# Schematic.net
KiCad netlist of a schematic drawn in Altium Designer
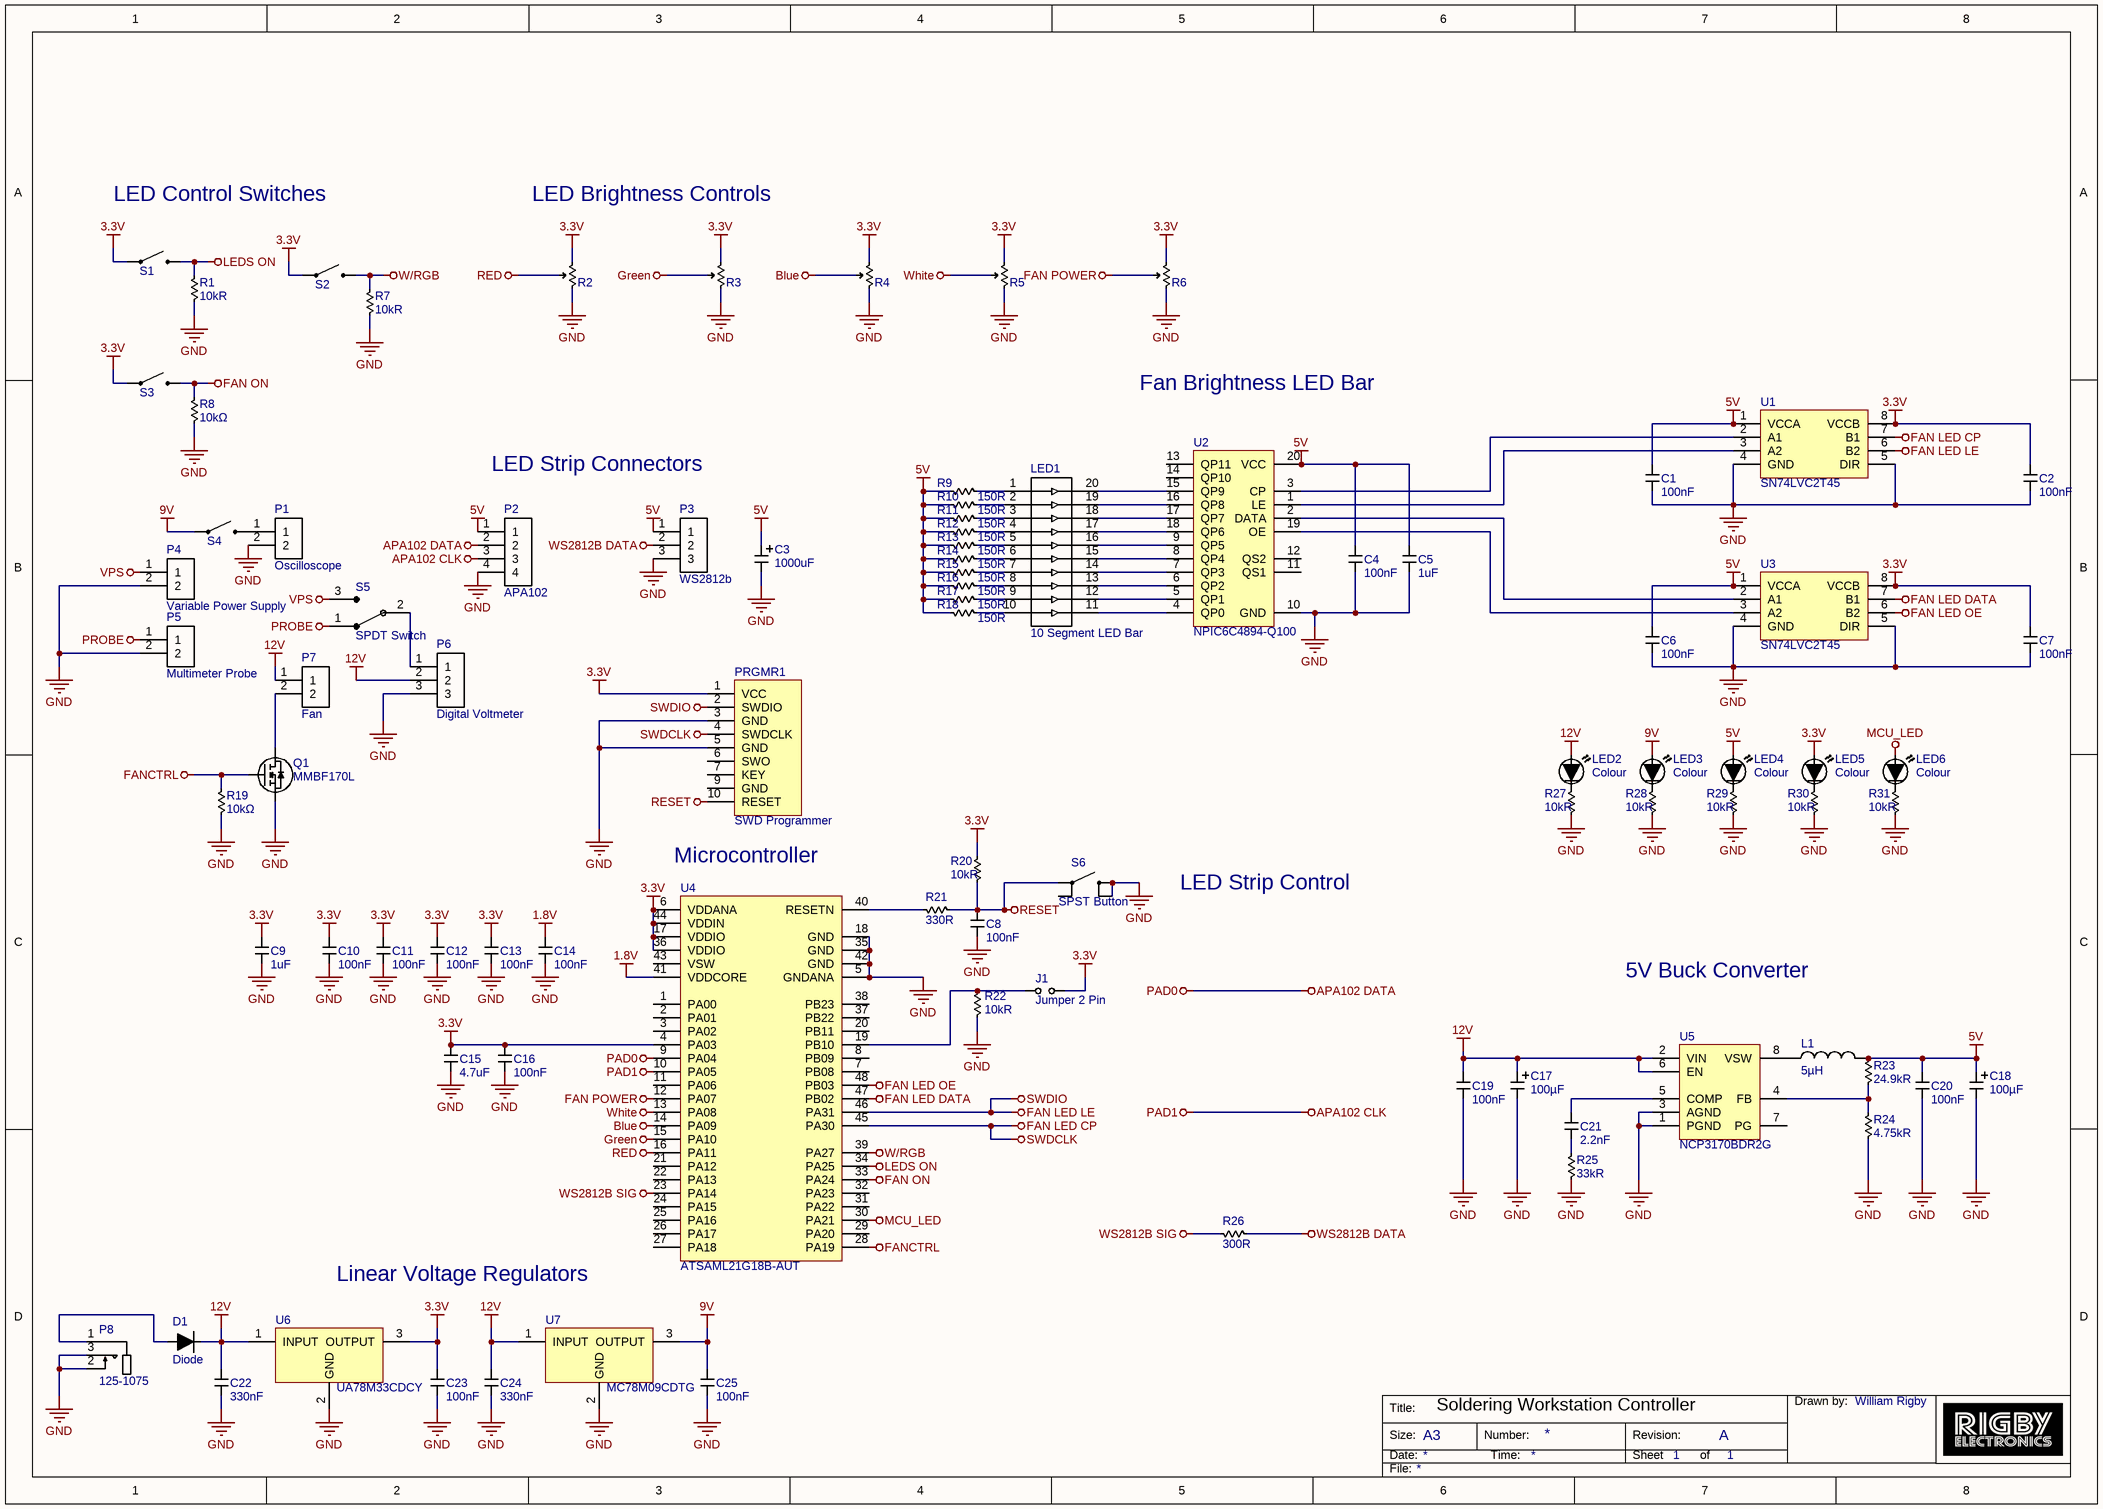
[diagram p0: Schematic.SchDoc]

(export (version "E")
  (design (tool "Eeschema 10.0.6"))
  (components
    (comp (ref "C1")
      (value "100nF")
      (footprint "0603")
      (description "Capacitor")
      (libsource (lib "Rigby Electronics Schematic Library") (part "Capacitor"))
    )
    (comp (ref "C2")
      (value "100nF")
      (footprint "0603")
      (description "Capacitor")
      (libsource (lib "Rigby Electronics Schematic Library") (part "Capacitor"))
    )
    (comp (ref "C3")
      (value "1000uF")
      (footprint "RS 711-0987")
      (description "Polarized Capacitor")
      (libsource (lib "Rigby Electronics Schematic Library") (part "Capacitor Polarized"))
    )
    (comp (ref "C4")
      (value "100nF")
      (footprint "0603")
      (description "Capacitor")
      (libsource (lib "Rigby Electronics Schematic Library") (part "Capacitor"))
    )
    (comp (ref "C5")
      (value "1uF")
      (footprint "0805")
      (description "Capacitor")
      (libsource (lib "Rigby Electronics Schematic Library") (part "Capacitor"))
    )
    (comp (ref "C6")
      (value "100nF")
      (footprint "0603")
      (description "Capacitor")
      (libsource (lib "Rigby Electronics Schematic Library") (part "Capacitor"))
    )
    (comp (ref "C7")
      (value "100nF")
      (footprint "0603")
      (description "Capacitor")
      (libsource (lib "Rigby Electronics Schematic Library") (part "Capacitor"))
    )
    (comp (ref "C8")
      (value "100nF")
      (footprint "0603")
      (description "Capacitor")
      (libsource (lib "Rigby Electronics Schematic Library") (part "Capacitor"))
    )
    (comp (ref "C9")
      (value "1uF")
      (footprint "0805")
      (description "Capacitor")
      (libsource (lib "Rigby Electronics Schematic Library") (part "Capacitor"))
    )
    (comp (ref "C10")
      (value "100nF")
      (footprint "0603")
      (description "Capacitor")
      (libsource (lib "Rigby Electronics Schematic Library") (part "Capacitor"))
    )
    (comp (ref "C11")
      (value "100nF")
      (footprint "0603")
      (description "Capacitor")
      (libsource (lib "Rigby Electronics Schematic Library") (part "Capacitor"))
    )
    (comp (ref "C12")
      (value "100nF")
      (footprint "0603")
      (description "Capacitor")
      (libsource (lib "Rigby Electronics Schematic Library") (part "Capacitor"))
    )
    (comp (ref "C13")
      (value "100nF")
      (footprint "0603")
      (description "Capacitor")
      (libsource (lib "Rigby Electronics Schematic Library") (part "Capacitor"))
    )
    (comp (ref "C14")
      (value "100nF")
      (footprint "0603")
      (description "Capacitor")
      (libsource (lib "Rigby Electronics Schematic Library") (part "Capacitor"))
    )
    (comp (ref "C15")
      (value "4.7uF")
      (footprint "0805")
      (description "Capacitor")
      (libsource (lib "Rigby Electronics Schematic Library") (part "Capacitor"))
    )
    (comp (ref "C16")
      (value "100nF")
      (footprint "0603")
      (description "Capacitor")
      (libsource (lib "Rigby Electronics Schematic Library") (part "Capacitor"))
    )
    (comp (ref "C17")
      (value "100µF")
      (footprint "Nichon UCD0J102MNL1GS")
      (description "Polarized Capacitor")
      (libsource (lib "Rigby Electronics Schematic Library") (part "Capacitor Polarized"))
    )
    (comp (ref "C18")
      (value "100µF")
      (footprint "Nichon UCD0J102MNL1GS")
      (description "Polarized Capacitor")
      (libsource (lib "Rigby Electronics Schematic Library") (part "Capacitor Polarized"))
    )
    (comp (ref "C19")
      (value "100nF")
      (footprint "0603")
      (description "Capacitor")
      (libsource (lib "Rigby Electronics Schematic Library") (part "Capacitor"))
    )
    (comp (ref "C20")
      (value "100nF")
      (footprint "0603")
      (description "Capacitor")
      (libsource (lib "Rigby Electronics Schematic Library") (part "Capacitor"))
    )
    (comp (ref "C21")
      (value "2.2nF")
      (footprint "Rigby Electronics Footprint Library:0603")
      (description "Capacitor")
      (libsource (lib "Rigby Electronics Schematic Library") (part "Capacitor"))
    )
    (comp (ref "C22")
      (value "330nF")
      (footprint "Rigby Electronics Footprint Library:0603")
      (description "Capacitor")
      (libsource (lib "Rigby Electronics Schematic Library") (part "Capacitor"))
    )
    (comp (ref "C23")
      (value "100nF")
      (footprint "Rigby Electronics Footprint Library:0603")
      (description "Capacitor")
      (libsource (lib "Rigby Electronics Schematic Library") (part "Capacitor"))
    )
    (comp (ref "C24")
      (value "330nF")
      (footprint "Rigby Electronics Footprint Library:0603")
      (description "Capacitor")
      (libsource (lib "Rigby Electronics Schematic Library") (part "Capacitor"))
    )
    (comp (ref "C25")
      (value "100nF")
      (footprint "Rigby Electronics Footprint Library:0603")
      (description "Capacitor")
      (libsource (lib "Rigby Electronics Schematic Library") (part "Capacitor"))
    )
    (comp (ref "D1")
      (value "Diode")
      (footprint "S5DC-13-F")
      (libsource (lib "Rigby Electronics Schematic Library") (part "Diode"))
    )
    (comp (ref "J1")
      (value "Jumper 2 Pin")
      (footprint "Jumper 2 Pins")
      (description "2 Pin Jumper")
      (libsource (lib "Rigby Electronics Schematic Library") (part "Jumper 2 Pin"))
    )
    (comp (ref "L1")
      (value "5µH")
      (footprint "SRU1038-5R0Y")
      (description "Inductor")
      (libsource (lib "Rigby Electronics Schematic Library") (part "Inductor"))
    )
    (comp (ref "LED1")
      (value "10 Segment LED Bar")
      (footprint "LED Bar 10 Segment")
      (libsource (lib "Rigby Electronics Schematic Library") (part "LED BAR"))
    )
    (comp (ref "LED2")
      (value "Colour")
      (footprint "0603LED")
      (description "Light Emitting Diode")
      (libsource (lib "Rigby Electronics Schematic Library") (part "LED"))
    )
    (comp (ref "LED3")
      (value "Colour")
      (footprint "0603LED")
      (description "Light Emitting Diode")
      (libsource (lib "Rigby Electronics Schematic Library") (part "LED"))
    )
    (comp (ref "LED4")
      (value "Colour")
      (footprint "0603LED")
      (description "Light Emitting Diode")
      (libsource (lib "Rigby Electronics Schematic Library") (part "LED"))
    )
    (comp (ref "LED5")
      (value "Colour")
      (footprint "0603LED")
      (description "Light Emitting Diode")
      (libsource (lib "Rigby Electronics Schematic Library") (part "LED"))
    )
    (comp (ref "LED6")
      (value "Colour")
      (footprint "0603LED")
      (description "Light Emitting Diode")
      (libsource (lib "Rigby Electronics Schematic Library") (part "LED"))
    )
    (comp (ref "P1")
      (value "Oscilloscope")
      (footprint "S2B-XH-A(LF)(SN)")
      (description "2 Pin Header")
      (libsource (lib "Rigby Electronics Schematic Library") (part "Header 2"))
    )
    (comp (ref "P2")
      (value "APA102")
      (footprint "S4B-XH-A(LF)(SN)")
      (description "4 Pin Header")
      (libsource (lib "Rigby Electronics Schematic Library") (part "Header 4"))
    )
    (comp (ref "P3")
      (value "WS2812b")
      (footprint "S3B-XH-A(LF)(SN)")
      (description "3 Pin Header")
      (libsource (lib "Rigby Electronics Schematic Library") (part "Header 3"))
    )
    (comp (ref "P4")
      (value "Variable Power Supply")
      (footprint "S2B-XH-A(LF)(SN)")
      (description "2 Pin Header")
      (libsource (lib "Rigby Electronics Schematic Library") (part "Header 2"))
    )
    (comp (ref "P5")
      (value "Multimeter Probe")
      (footprint "S2B-XH-A(LF)(SN)")
      (description "2 Pin Header")
      (libsource (lib "Rigby Electronics Schematic Library") (part "Header 2"))
    )
    (comp (ref "P6")
      (value "Digital Voltmeter")
      (footprint "S3B-XH-A(LF)(SN)")
      (description "3 Pin Header")
      (libsource (lib "Rigby Electronics Schematic Library") (part "Header 3"))
    )
    (comp (ref "P7")
      (value "Fan")
      (footprint "S2B-XH-A(LF)(SN)")
      (description "2 Pin Header")
      (libsource (lib "Rigby Electronics Schematic Library") (part "Header 2"))
    )
    (comp (ref "P8")
      (value "125-1075")
      (footprint "RS-PRO 125-1075")
      (description "2.1mm DC Power Socket")
      (libsource (lib "Rigby Electronics Schematic Library") (part "DC Power Connector RS-PRO 125-1075"))
    )
    (comp (ref "PRGMR1")
      (value "SWD Programmer")
      (footprint "HEADER 5X2")
      (description "Atmel ICE Programmer")
      (libsource (lib "Rigby Electronics Schematic Library") (part "SWD Programmer"))
    )
    (comp (ref "Q1")
      (value "MMBF170L")
      (footprint "MMBF170L")
      (description "N-Channel Logic Level MOSFET")
      (libsource (lib "Rigby Electronics Schematic Library") (part "MMBF170L"))
    )
    (comp (ref "R1")
      (value "10kR")
      (footprint "Rigby Electronics Footprint Library:0603")
      (description "Standard Resistor")
      (libsource (lib "") (part "Resistor_1"))
    )
    (comp (ref "R2")
      (value "Potentiometer")
      (footprint "S3B-XH-A(LF)(SN)")
      (libsource (lib "Rigby Electronics Schematic Library") (part "Potentiometer"))
    )
    (comp (ref "R3")
      (value "Potentiometer")
      (footprint "S3B-XH-A(LF)(SN)")
      (libsource (lib "Rigby Electronics Schematic Library") (part "Potentiometer"))
    )
    (comp (ref "R4")
      (value "Potentiometer")
      (footprint "S3B-XH-A(LF)(SN)")
      (libsource (lib "Rigby Electronics Schematic Library") (part "Potentiometer"))
    )
    (comp (ref "R5")
      (value "Potentiometer")
      (footprint "S3B-XH-A(LF)(SN)")
      (libsource (lib "Rigby Electronics Schematic Library") (part "Potentiometer"))
    )
    (comp (ref "R6")
      (value "Potentiometer")
      (footprint "S3B-XH-A(LF)(SN)")
      (libsource (lib "Rigby Electronics Schematic Library") (part "Potentiometer"))
    )
    (comp (ref "R7")
      (value "10kR")
      (footprint "Rigby Electronics Footprint Library:0603")
      (description "Standard Resistor")
      (libsource (lib "") (part "Resistor_1"))
    )
    (comp (ref "R8")
      (value "10kΩ")
      (footprint "Rigby Electronics Footprint Library:0603")
      (description "Standard Resistor")
      (libsource (lib "") (part "Resistor_1"))
    )
    (comp (ref "R9")
      (value "150R")
      (footprint "Rigby Electronics Footprint Library:0603")
      (description "Standard Resistor")
      (libsource (lib "Rigby Electronics Schematic Library") (part "Resistor"))
    )
    (comp (ref "R10")
      (value "150R")
      (footprint "Rigby Electronics Footprint Library:0603")
      (description "Standard Resistor")
      (libsource (lib "Rigby Electronics Schematic Library") (part "Resistor"))
    )
    (comp (ref "R11")
      (value "150R")
      (footprint "Rigby Electronics Footprint Library:0603")
      (description "Standard Resistor")
      (libsource (lib "Rigby Electronics Schematic Library") (part "Resistor"))
    )
    (comp (ref "R12")
      (value "150R")
      (footprint "Rigby Electronics Footprint Library:0603")
      (description "Standard Resistor")
      (libsource (lib "Rigby Electronics Schematic Library") (part "Resistor"))
    )
    (comp (ref "R13")
      (value "150R")
      (footprint "Rigby Electronics Footprint Library:0603")
      (description "Standard Resistor")
      (libsource (lib "Rigby Electronics Schematic Library") (part "Resistor"))
    )
    (comp (ref "R14")
      (value "150R")
      (footprint "Rigby Electronics Footprint Library:0603")
      (description "Standard Resistor")
      (libsource (lib "Rigby Electronics Schematic Library") (part "Resistor"))
    )
    (comp (ref "R15")
      (value "150R")
      (footprint "Rigby Electronics Footprint Library:0603")
      (description "Standard Resistor")
      (libsource (lib "Rigby Electronics Schematic Library") (part "Resistor"))
    )
    (comp (ref "R16")
      (value "150R")
      (footprint "Rigby Electronics Footprint Library:0603")
      (description "Standard Resistor")
      (libsource (lib "Rigby Electronics Schematic Library") (part "Resistor"))
    )
    (comp (ref "R17")
      (value "150R")
      (footprint "Rigby Electronics Footprint Library:0603")
      (description "Standard Resistor")
      (libsource (lib "Rigby Electronics Schematic Library") (part "Resistor"))
    )
    (comp (ref "R18")
      (value "150R")
      (footprint "Rigby Electronics Footprint Library:0603")
      (description "Standard Resistor")
      (libsource (lib "Rigby Electronics Schematic Library") (part "Resistor"))
    )
    (comp (ref "R19")
      (value "10kΩ")
      (footprint "Rigby Electronics Footprint Library:0603")
      (description "Standard Resistor")
      (libsource (lib "") (part "Resistor_1"))
    )
    (comp (ref "R20")
      (value "10kR")
      (footprint "0603")
      (description "Standard Resistor")
      (libsource (lib "Rigby Electronics Library") (part "Resistor"))
    )
    (comp (ref "R21")
      (value "330R")
      (footprint "0603")
      (description "Standard Resistor")
      (libsource (lib "") (part "Resistor_1"))
    )
    (comp (ref "R22")
      (value "10kR")
      (footprint "0603")
      (description "Standard Resistor")
      (libsource (lib "Rigby Electronics Library") (part "Resistor"))
    )
    (comp (ref "R23")
      (value "24.9kR")
      (footprint "0603")
      (description "Standard Resistor")
      (libsource (lib "Rigby Electronics Library") (part "Resistor"))
    )
    (comp (ref "R24")
      (value "4.75kR")
      (footprint "0603")
      (description "Standard Resistor")
      (libsource (lib "Rigby Electronics Library") (part "Resistor"))
    )
    (comp (ref "R25")
      (value "33kR")
      (footprint "0603")
      (description "Standard Resistor")
      (libsource (lib "Rigby Electronics Library") (part "Resistor"))
    )
    (comp (ref "R26")
      (value "300R")
      (footprint "0603")
      (description "Standard Resistor")
      (libsource (lib "Rigby Electronics Library") (part "Resistor"))
    )
    (comp (ref "R27")
      (value "10kR")
      (footprint "0603")
      (description "Standard Resistor")
      (libsource (lib "Rigby Electronics Library") (part "Resistor"))
    )
    (comp (ref "R28")
      (value "10kR")
      (footprint "0603")
      (description "Standard Resistor")
      (libsource (lib "Rigby Electronics Library") (part "Resistor"))
    )
    (comp (ref "R29")
      (value "10kR")
      (footprint "0603")
      (description "Standard Resistor")
      (libsource (lib "Rigby Electronics Library") (part "Resistor"))
    )
    (comp (ref "R30")
      (value "10kR")
      (footprint "0603")
      (description "Standard Resistor")
      (libsource (lib "Rigby Electronics Library") (part "Resistor"))
    )
    (comp (ref "R31")
      (value "10kR")
      (footprint "0603")
      (description "Standard Resistor")
      (libsource (lib "Rigby Electronics Library") (part "Resistor"))
    )
    (comp (ref "S1")
      (value "SPST Switch")
      (footprint "S2B-XH-A(LF)(SN)")
      (libsource (lib "Rigby Electronics Schematic Library") (part "SPST Switch"))
    )
    (comp (ref "S2")
      (value "SPST Switch")
      (footprint "S2B-XH-A(LF)(SN)")
      (libsource (lib "Rigby Electronics Schematic Library") (part "SPST Switch"))
    )
    (comp (ref "S3")
      (value "SPST Switch")
      (footprint "S2B-XH-A(LF)(SN)")
      (libsource (lib "Rigby Electronics Schematic Library") (part "SPST Switch"))
    )
    (comp (ref "S4")
      (value "SPST Switch")
      (footprint "S2B-XH-A(LF)(SN)")
      (libsource (lib "Rigby Electronics Schematic Library") (part "SPST Switch"))
    )
    (comp (ref "S5")
      (value "SPDT Switch")
      (footprint "S3B-XH-A(LF)(SN)")
      (libsource (lib "Rigby Electronics Schematic Library") (part "SPDT Switch"))
    )
    (comp (ref "S6")
      (value "SPST Button")
      (footprint "TE 4-1437565-1")
      (description "SPST Switch")
      (libsource (lib "Rigby Electronics Schematic Library") (part "SPST Button"))
    )
    (comp (ref "U1")
      (value "SN74LVC2T45")
      (footprint "SN74LVC2T45DCU")
      (description "Dual-Bit Bus Transceiver")
      (libsource (lib "Rigby Electronics Schematic Library") (part "SN74LVC2T45"))
    )
    (comp (ref "U2")
      (value "NPIC6C4894-Q100")
      (footprint "NPIC6C4894-Q100")
      (description "Power logic 12-bit shift register; open-drain output")
      (libsource (lib "Rigby Electronics Schematic Library") (part "NPIC6C4894-Q100"))
    )
    (comp (ref "U3")
      (value "SN74LVC2T45")
      (footprint "SN74LVC2T45DCU")
      (description "Dual-Bit Bus Transceiver")
      (libsource (lib "Rigby Electronics Schematic Library") (part "SN74LVC2T45"))
    )
    (comp (ref "U4")
      (value "ATSAML21G18B-AUT")
      (footprint "ATSAMD21G18A-AU")
      (description "32-Bit Microcontroller, 48MHz, 256kB")
      (libsource (lib "Rigby Electronics Schematic Library") (part "ATSAML21G18B-AUT"))
    )
    (comp (ref "U5")
      (value "NCP3170BDR2G")
      (footprint "NCP3170BDR2G")
      (description "Synchronous PWM Switching Converter 3A")
      (libsource (lib "Rigby Electronics Schematic Library") (part "NCP3170BDR2G"))
    )
    (comp (ref "U6")
      (value "UA78M33CDCY")
      (footprint "UA78M33CDCY")
      (description "Linear Voltage Regulator 3.3V 500mA 25V Input")
      (libsource (lib "Rigby Electronics Schematic Library") (part "UA78M33CDCY"))
    )
    (comp (ref "U7")
      (value "MC78M09CDTG")
      (footprint "MC78M09CDTG")
      (description "Linear Voltage Regulator 9V 700mA 35V Input")
      (libsource (lib "Rigby Electronics Schematic Library") (part "MC78M09CDTG"))
    )
  )
  (nets
    (net (code "1") (name "1.8V") (class "Default")
      (node (ref "C14") (pin "1") (pinfunction "1_1") (pintype "passive"))
      (node (ref "U4") (pin "41") (pinfunction "VDDCORE_41") (pintype "passive"))
    )
    (net (code "2") (name "3.3V") (class "Default")
      (node (ref "C10") (pin "1") (pinfunction "1_1") (pintype "passive"))
      (node (ref "C11") (pin "1") (pinfunction "1_1") (pintype "passive"))
      (node (ref "C12") (pin "1") (pinfunction "1_1") (pintype "passive"))
      (node (ref "C13") (pin "1") (pinfunction "1_1") (pintype "passive"))
      (node (ref "C15") (pin "1") (pinfunction "1_1") (pintype "passive"))
      (node (ref "C16") (pin "1") (pinfunction "1_1") (pintype "passive"))
      (node (ref "C2") (pin "1") (pinfunction "1_1") (pintype "passive"))
      (node (ref "C23") (pin "1") (pinfunction "1_1") (pintype "passive"))
      (node (ref "C7") (pin "1") (pinfunction "1_1") (pintype "passive"))
      (node (ref "C9") (pin "1") (pinfunction "1_1") (pintype "passive"))
      (node (ref "J1") (pin "1") (pinfunction "1_1") (pintype "passive"))
      (node (ref "LED5") (pin "1") (pinfunction "1_1") (pintype "passive"))
      (node (ref "PRGMR1") (pin "1") (pinfunction "VCC_1") (pintype "passive"))
      (node (ref "R2") (pin "3") (pinfunction "3_3") (pintype "passive"))
      (node (ref "R20") (pin "2") (pinfunction "2_2") (pintype "passive"))
      (node (ref "R3") (pin "3") (pinfunction "3_3") (pintype "passive"))
      (node (ref "R4") (pin "3") (pinfunction "3_3") (pintype "passive"))
      (node (ref "R5") (pin "3") (pinfunction "3_3") (pintype "passive"))
      (node (ref "R6") (pin "3") (pinfunction "3_3") (pintype "passive"))
      (node (ref "S1") (pin "1") (pinfunction "1_1") (pintype "passive"))
      (node (ref "S2") (pin "1") (pinfunction "1_1") (pintype "passive"))
      (node (ref "S3") (pin "1") (pinfunction "1_1") (pintype "passive"))
      (node (ref "U1") (pin "8") (pinfunction "VCCB_8") (pintype "passive"))
      (node (ref "U3") (pin "8") (pinfunction "VCCB_8") (pintype "passive"))
      (node (ref "U4") (pin "17") (pinfunction "VDDIO_17") (pintype "passive"))
      (node (ref "U4") (pin "36") (pinfunction "VDDIO_36") (pintype "passive"))
      (node (ref "U4") (pin "4") (pinfunction "PA03_4") (pintype "passive"))
      (node (ref "U4") (pin "44") (pinfunction "VDDIN_44") (pintype "passive"))
      (node (ref "U4") (pin "6") (pinfunction "VDDANA_6") (pintype "passive"))
      (node (ref "U6") (pin "3") (pinfunction "OUTPUT_3") (pintype "passive"))
    )
    (net (code "3") (name "5V") (class "Default")
      (node (ref "C1") (pin "1") (pinfunction "1_1") (pintype "passive"))
      (node (ref "C18") (pin "1") (pinfunction "1_1") (pintype "passive"))
      (node (ref "C20") (pin "1") (pinfunction "1_1") (pintype "passive"))
      (node (ref "C3") (pin "1") (pinfunction "1_1") (pintype "passive"))
      (node (ref "C4") (pin "1") (pinfunction "1_1") (pintype "passive"))
      (node (ref "C5") (pin "1") (pinfunction "1_1") (pintype "passive"))
      (node (ref "C6") (pin "1") (pinfunction "1_1") (pintype "passive"))
      (node (ref "L1") (pin "1") (pinfunction "1_1") (pintype "passive"))
      (node (ref "LED4") (pin "1") (pinfunction "1_1") (pintype "passive"))
      (node (ref "P2") (pin "1") (pinfunction "1_1") (pintype "passive"))
      (node (ref "P3") (pin "1") (pinfunction "1_1") (pintype "passive"))
      (node (ref "R10") (pin "2") (pinfunction "2_2") (pintype "passive"))
      (node (ref "R11") (pin "2") (pinfunction "2_2") (pintype "passive"))
      (node (ref "R12") (pin "2") (pinfunction "2_2") (pintype "passive"))
      (node (ref "R13") (pin "2") (pinfunction "2_2") (pintype "passive"))
      (node (ref "R14") (pin "2") (pinfunction "2_2") (pintype "passive"))
      (node (ref "R15") (pin "2") (pinfunction "2_2") (pintype "passive"))
      (node (ref "R16") (pin "2") (pinfunction "2_2") (pintype "passive"))
      (node (ref "R17") (pin "2") (pinfunction "2_2") (pintype "passive"))
      (node (ref "R18") (pin "2") (pinfunction "2_2") (pintype "passive"))
      (node (ref "R23") (pin "2") (pinfunction "2_2") (pintype "passive"))
      (node (ref "R9") (pin "2") (pinfunction "2_2") (pintype "passive"))
      (node (ref "U1") (pin "1") (pinfunction "VCCA_1") (pintype "passive"))
      (node (ref "U2") (pin "20") (pinfunction "VCC_20") (pintype "passive"))
      (node (ref "U3") (pin "1") (pinfunction "VCCA_1") (pintype "passive"))
    )
    (net (code "4") (name "9V") (class "Default")
      (node (ref "C25") (pin "1") (pinfunction "1_1") (pintype "passive"))
      (node (ref "LED3") (pin "1") (pinfunction "1_1") (pintype "passive"))
      (node (ref "S4") (pin "1") (pinfunction "1_1") (pintype "passive"))
      (node (ref "U7") (pin "3") (pinfunction "OUTPUT_3") (pintype "passive"))
    )
    (net (code "5") (name "12V") (class "Default")
      (node (ref "C17") (pin "1") (pinfunction "1_1") (pintype "passive"))
      (node (ref "C19") (pin "1") (pinfunction "1_1") (pintype "passive"))
      (node (ref "C22") (pin "1") (pinfunction "1_1") (pintype "passive"))
      (node (ref "C24") (pin "1") (pinfunction "1_1") (pintype "passive"))
      (node (ref "D1") (pin "2") (pinfunction "2_2") (pintype "passive"))
      (node (ref "LED2") (pin "1") (pinfunction "1_1") (pintype "passive"))
      (node (ref "P6") (pin "2") (pinfunction "2_2") (pintype "passive"))
      (node (ref "P7") (pin "1") (pinfunction "1_1") (pintype "passive"))
      (node (ref "U5") (pin "2") (pinfunction "VIN_2") (pintype "passive"))
      (node (ref "U5") (pin "6") (pinfunction "EN_6") (pintype "passive"))
      (node (ref "U6") (pin "1") (pinfunction "INPUT_1") (pintype "passive"))
      (node (ref "U7") (pin "1") (pinfunction "INPUT_1") (pintype "passive"))
    )
    (net (code "6") (name "APA102 CLK") (class "Default")
      (node (ref "P2") (pin "3") (pinfunction "3_3") (pintype "passive"))
      (node (ref "U4") (pin "10") (pinfunction "PA05_10") (pintype "passive"))
    )
    (net (code "7") (name "APA102 DATA") (class "Default")
      (node (ref "P2") (pin "2") (pinfunction "2_2") (pintype "passive"))
      (node (ref "U4") (pin "9") (pinfunction "PA04_9") (pintype "passive"))
    )
    (net (code "8") (name "Blue") (class "Default")
      (node (ref "R4") (pin "2") (pinfunction "2_2") (pintype "passive"))
      (node (ref "U4") (pin "14") (pinfunction "PA09_14") (pintype "passive"))
    )
    (net (code "9") (name "FAN LED CP") (class "Default")
      (node (ref "PRGMR1") (pin "4") (pinfunction "SWDCLK_4") (pintype "passive"))
      (node (ref "U1") (pin "7") (pinfunction "B1_7") (pintype "passive"))
      (node (ref "U4") (pin "45") (pinfunction "PA30_45") (pintype "passive"))
    )
    (net (code "10") (name "FAN LED DATA") (class "Default")
      (node (ref "U3") (pin "7") (pinfunction "B1_7") (pintype "passive"))
      (node (ref "U4") (pin "47") (pinfunction "PB02_47") (pintype "passive"))
    )
    (net (code "11") (name "FAN LED LE") (class "Default")
      (node (ref "PRGMR1") (pin "2") (pinfunction "SWDIO_2") (pintype "passive"))
      (node (ref "U1") (pin "6") (pinfunction "B2_6") (pintype "passive"))
      (node (ref "U4") (pin "46") (pinfunction "PA31_46") (pintype "passive"))
    )
    (net (code "12") (name "FAN LED OE") (class "Default")
      (node (ref "U3") (pin "6") (pinfunction "B2_6") (pintype "passive"))
      (node (ref "U4") (pin "48") (pinfunction "PB03_48") (pintype "passive"))
    )
    (net (code "13") (name "FAN ON") (class "Default")
      (node (ref "R8") (pin "2") (pinfunction "2_2") (pintype "passive"))
      (node (ref "S3") (pin "2") (pinfunction "2_2") (pintype "passive"))
      (node (ref "U4") (pin "33") (pinfunction "PA24_33") (pintype "passive"))
    )
    (net (code "14") (name "FAN POWER") (class "Default")
      (node (ref "R6") (pin "2") (pinfunction "2_2") (pintype "passive"))
      (node (ref "U4") (pin "12") (pinfunction "PA07_12") (pintype "passive"))
    )
    (net (code "15") (name "FANCTRL") (class "Default")
      (node (ref "Q1") (pin "G") (pinfunction "G_G") (pintype "passive"))
      (node (ref "R19") (pin "2") (pinfunction "2_2") (pintype "passive"))
      (node (ref "U4") (pin "28") (pinfunction "PA19_28") (pintype "passive"))
    )
    (net (code "16") (name "GND") (class "Default")
      (node (ref "C1") (pin "2") (pinfunction "2_2") (pintype "passive"))
      (node (ref "C10") (pin "2") (pinfunction "2_2") (pintype "passive"))
      (node (ref "C11") (pin "2") (pinfunction "2_2") (pintype "passive"))
      (node (ref "C12") (pin "2") (pinfunction "2_2") (pintype "passive"))
      (node (ref "C13") (pin "2") (pinfunction "2_2") (pintype "passive"))
      (node (ref "C14") (pin "2") (pinfunction "2_2") (pintype "passive"))
      (node (ref "C15") (pin "2") (pinfunction "2_2") (pintype "passive"))
      (node (ref "C16") (pin "2") (pinfunction "2_2") (pintype "passive"))
      (node (ref "C17") (pin "2") (pinfunction "2_2") (pintype "passive"))
      (node (ref "C18") (pin "2") (pinfunction "2_2") (pintype "passive"))
      (node (ref "C19") (pin "2") (pinfunction "2_2") (pintype "passive"))
      (node (ref "C2") (pin "2") (pinfunction "2_2") (pintype "passive"))
      (node (ref "C20") (pin "2") (pinfunction "2_2") (pintype "passive"))
      (node (ref "C22") (pin "2") (pinfunction "2_2") (pintype "passive"))
      (node (ref "C23") (pin "2") (pinfunction "2_2") (pintype "passive"))
      (node (ref "C24") (pin "2") (pinfunction "2_2") (pintype "passive"))
      (node (ref "C25") (pin "2") (pinfunction "2_2") (pintype "passive"))
      (node (ref "C3") (pin "2") (pinfunction "2_2") (pintype "passive"))
      (node (ref "C4") (pin "2") (pinfunction "2_2") (pintype "passive"))
      (node (ref "C5") (pin "2") (pinfunction "2_2") (pintype "passive"))
      (node (ref "C6") (pin "2") (pinfunction "2_2") (pintype "passive"))
      (node (ref "C7") (pin "2") (pinfunction "2_2") (pintype "passive"))
      (node (ref "C8") (pin "2") (pinfunction "2_2") (pintype "passive"))
      (node (ref "C9") (pin "2") (pinfunction "2_2") (pintype "passive"))
      (node (ref "P1") (pin "2") (pinfunction "2_2") (pintype "passive"))
      (node (ref "P2") (pin "4") (pinfunction "4_4") (pintype "passive"))
      (node (ref "P3") (pin "3") (pinfunction "3_3") (pintype "passive"))
      (node (ref "P4") (pin "2") (pinfunction "2_2") (pintype "passive"))
      (node (ref "P5") (pin "2") (pinfunction "2_2") (pintype "passive"))
      (node (ref "P6") (pin "3") (pinfunction "3_3") (pintype "passive"))
      (node (ref "P8") (pin "2") (pinfunction "2_2") (pintype "passive"))
      (node (ref "P8") (pin "3") (pinfunction "3_3") (pintype "passive"))
      (node (ref "PRGMR1") (pin "3") (pinfunction "GND_3") (pintype "passive"))
      (node (ref "PRGMR1") (pin "5") (pinfunction "GND_5") (pintype "passive"))
      (node (ref "Q1") (pin "S") (pinfunction "S_S") (pintype "passive"))
      (node (ref "R1") (pin "1") (pinfunction "1_1") (pintype "passive"))
      (node (ref "R19") (pin "1") (pinfunction "1_1") (pintype "passive"))
      (node (ref "R2") (pin "1") (pinfunction "1_1") (pintype "passive"))
      (node (ref "R22") (pin "1") (pinfunction "1_1") (pintype "passive"))
      (node (ref "R24") (pin "1") (pinfunction "1_1") (pintype "passive"))
      (node (ref "R25") (pin "1") (pinfunction "1_1") (pintype "passive"))
      (node (ref "R27") (pin "1") (pinfunction "1_1") (pintype "passive"))
      (node (ref "R28") (pin "1") (pinfunction "1_1") (pintype "passive"))
      (node (ref "R29") (pin "1") (pinfunction "1_1") (pintype "passive"))
      (node (ref "R3") (pin "1") (pinfunction "1_1") (pintype "passive"))
      (node (ref "R30") (pin "1") (pinfunction "1_1") (pintype "passive"))
      (node (ref "R31") (pin "1") (pinfunction "1_1") (pintype "passive"))
      (node (ref "R4") (pin "1") (pinfunction "1_1") (pintype "passive"))
      (node (ref "R5") (pin "1") (pinfunction "1_1") (pintype "passive"))
      (node (ref "R6") (pin "1") (pinfunction "1_1") (pintype "passive"))
      (node (ref "R7") (pin "1") (pinfunction "1_1") (pintype "passive"))
      (node (ref "R8") (pin "1") (pinfunction "1_1") (pintype "passive"))
      (node (ref "S6") (pin "3") (pinfunction "3_3") (pintype "passive"))
      (node (ref "S6") (pin "4") (pinfunction "4_4") (pintype "passive"))
      (node (ref "U1") (pin "4") (pinfunction "GND_4") (pintype "passive"))
      (node (ref "U1") (pin "5") (pinfunction "DIR_5") (pintype "passive"))
      (node (ref "U2") (pin "10") (pinfunction "GND_10") (pintype "passive"))
      (node (ref "U3") (pin "4") (pinfunction "GND_4") (pintype "passive"))
      (node (ref "U3") (pin "5") (pinfunction "DIR_5") (pintype "passive"))
      (node (ref "U4") (pin "18") (pinfunction "GND_18") (pintype "passive"))
      (node (ref "U4") (pin "35") (pinfunction "GND_35") (pintype "passive"))
      (node (ref "U4") (pin "42") (pinfunction "GND_42") (pintype "passive"))
      (node (ref "U4") (pin "5") (pinfunction "GNDANA_5") (pintype "passive"))
      (node (ref "U5") (pin "1") (pinfunction "PGND_1") (pintype "passive"))
      (node (ref "U5") (pin "3") (pinfunction "AGND_3") (pintype "passive"))
      (node (ref "U6") (pin "2") (pinfunction "GND_2") (pintype "passive"))
      (node (ref "U7") (pin "2") (pinfunction "GND_2") (pintype "passive"))
    )
    (net (code "17") (name "Green") (class "Default")
      (node (ref "R3") (pin "2") (pinfunction "2_2") (pintype "passive"))
      (node (ref "U4") (pin "15") (pinfunction "PA10_15") (pintype "passive"))
    )
    (net (code "18") (name "LEDS ON") (class "Default")
      (node (ref "R1") (pin "2") (pinfunction "2_2") (pintype "passive"))
      (node (ref "S1") (pin "2") (pinfunction "2_2") (pintype "passive"))
      (node (ref "U4") (pin "34") (pinfunction "PA25_34") (pintype "passive"))
    )
    (net (code "19") (name "MCU_LED") (class "Default")
      (node (ref "LED6") (pin "1") (pinfunction "1_1") (pintype "passive"))
      (node (ref "U4") (pin "30") (pinfunction "PA21_30") (pintype "passive"))
    )
    (net (code "20") (name "Net-(C21-Pad2)") (class "Default")
      (node (ref "C21") (pin "2") (pinfunction "2_2") (pintype "passive"))
      (node (ref "R25") (pin "2") (pinfunction "2_2") (pintype "passive"))
    )
    (net (code "21") (name "Net-(D1-Pad1)") (class "Default")
      (node (ref "D1") (pin "1") (pinfunction "1_1") (pintype "passive"))
      (node (ref "P8") (pin "1") (pinfunction "1_1") (pintype "passive"))
    )
    (net (code "22") (name "Net-(LED1-Pad1)") (class "Default")
      (node (ref "LED1") (pin "1") (pinfunction "1_1") (pintype "passive"))
      (node (ref "R9") (pin "1") (pinfunction "1_1") (pintype "passive"))
    )
    (net (code "23") (name "Net-(LED1-Pad2)") (class "Default")
      (node (ref "LED1") (pin "2") (pinfunction "2_2") (pintype "passive"))
      (node (ref "R10") (pin "1") (pinfunction "1_1") (pintype "passive"))
    )
    (net (code "24") (name "Net-(LED1-Pad3)") (class "Default")
      (node (ref "LED1") (pin "3") (pinfunction "3_3") (pintype "passive"))
      (node (ref "R11") (pin "1") (pinfunction "1_1") (pintype "passive"))
    )
    (net (code "25") (name "Net-(LED1-Pad4)") (class "Default")
      (node (ref "LED1") (pin "4") (pinfunction "4_4") (pintype "passive"))
      (node (ref "R12") (pin "1") (pinfunction "1_1") (pintype "passive"))
    )
    (net (code "26") (name "Net-(LED1-Pad5)") (class "Default")
      (node (ref "LED1") (pin "5") (pinfunction "5_5") (pintype "passive"))
      (node (ref "R13") (pin "1") (pinfunction "1_1") (pintype "passive"))
    )
    (net (code "27") (name "Net-(LED1-Pad6)") (class "Default")
      (node (ref "LED1") (pin "6") (pinfunction "6_6") (pintype "passive"))
      (node (ref "R14") (pin "1") (pinfunction "1_1") (pintype "passive"))
    )
    (net (code "28") (name "Net-(LED1-Pad7)") (class "Default")
      (node (ref "LED1") (pin "7") (pinfunction "7_7") (pintype "passive"))
      (node (ref "R15") (pin "1") (pinfunction "1_1") (pintype "passive"))
    )
    (net (code "29") (name "Net-(LED1-Pad8)") (class "Default")
      (node (ref "LED1") (pin "8") (pinfunction "8_8") (pintype "passive"))
      (node (ref "R16") (pin "1") (pinfunction "1_1") (pintype "passive"))
    )
    (net (code "30") (name "Net-(LED1-Pad9)") (class "Default")
      (node (ref "LED1") (pin "9") (pinfunction "9_9") (pintype "passive"))
      (node (ref "R17") (pin "1") (pinfunction "1_1") (pintype "passive"))
    )
    (net (code "31") (name "Net-(LED1-Pad10)") (class "Default")
      (node (ref "LED1") (pin "10") (pinfunction "10_10") (pintype "passive"))
      (node (ref "R18") (pin "1") (pinfunction "1_1") (pintype "passive"))
    )
    (net (code "32") (name "Net-(LED2-Pad2)") (class "Default")
      (node (ref "LED2") (pin "2") (pinfunction "2_2") (pintype "passive"))
      (node (ref "R27") (pin "2") (pinfunction "2_2") (pintype "passive"))
    )
    (net (code "33") (name "Net-(LED3-Pad2)") (class "Default")
      (node (ref "LED3") (pin "2") (pinfunction "2_2") (pintype "passive"))
      (node (ref "R28") (pin "2") (pinfunction "2_2") (pintype "passive"))
    )
    (net (code "34") (name "Net-(LED4-Pad2)") (class "Default")
      (node (ref "LED4") (pin "2") (pinfunction "2_2") (pintype "passive"))
      (node (ref "R29") (pin "2") (pinfunction "2_2") (pintype "passive"))
    )
    (net (code "35") (name "Net-(LED5-Pad2)") (class "Default")
      (node (ref "LED5") (pin "2") (pinfunction "2_2") (pintype "passive"))
      (node (ref "R30") (pin "2") (pinfunction "2_2") (pintype "passive"))
    )
    (net (code "36") (name "Net-(LED6-Pad2)") (class "Default")
      (node (ref "LED6") (pin "2") (pinfunction "2_2") (pintype "passive"))
      (node (ref "R31") (pin "2") (pinfunction "2_2") (pintype "passive"))
    )
    (net (code "37") (name "Net-(P1-Pad1)") (class "Default")
      (node (ref "P1") (pin "1") (pinfunction "1_1") (pintype "passive"))
      (node (ref "S4") (pin "2") (pinfunction "2_2") (pintype "passive"))
    )
    (net (code "38") (name "Net-(P6-Pad1)") (class "Default")
      (node (ref "P6") (pin "1") (pinfunction "1_1") (pintype "passive"))
      (node (ref "S5") (pin "2") (pinfunction "2_2") (pintype "passive"))
    )
    (net (code "39") (name "Net-(P7-Pad2)") (class "Default")
      (node (ref "P7") (pin "2") (pinfunction "2_2") (pintype "passive"))
      (node (ref "Q1") (pin "D") (pinfunction "D_D") (pintype "passive"))
    )
    (net (code "40") (name "Net-(U1-A1)") (class "Default")
      (node (ref "U1") (pin "2") (pinfunction "A1_2") (pintype "passive"))
      (node (ref "U2") (pin "3") (pinfunction "CP_3") (pintype "passive"))
    )
    (net (code "41") (name "Net-(U1-A2)") (class "Default")
      (node (ref "U1") (pin "3") (pinfunction "A2_3") (pintype "passive"))
      (node (ref "U2") (pin "1") (pinfunction "LE_1") (pintype "passive"))
    )
    (net (code "42") (name "Net-(U2-DATA)") (class "Default")
      (node (ref "U2") (pin "2") (pinfunction "DATA_2") (pintype "passive"))
      (node (ref "U3") (pin "2") (pinfunction "A1_2") (pintype "passive"))
    )
    (net (code "43") (name "Net-(U2-OE)") (class "Default")
      (node (ref "U2") (pin "19") (pinfunction "OE_19") (pintype "passive"))
      (node (ref "U3") (pin "3") (pinfunction "A2_3") (pintype "passive"))
    )
    (net (code "44") (name "Net-(U2-QP0)") (class "Default")
      (node (ref "LED1") (pin "11") (pinfunction "11_11") (pintype "passive"))
      (node (ref "U2") (pin "4") (pinfunction "QP0_4") (pintype "passive"))
    )
    (net (code "45") (name "Net-(U2-QP1)") (class "Default")
      (node (ref "LED1") (pin "12") (pinfunction "12_12") (pintype "passive"))
      (node (ref "U2") (pin "5") (pinfunction "QP1_5") (pintype "passive"))
    )
    (net (code "46") (name "Net-(U2-QP2)") (class "Default")
      (node (ref "LED1") (pin "13") (pinfunction "13_13") (pintype "passive"))
      (node (ref "U2") (pin "6") (pinfunction "QP2_6") (pintype "passive"))
    )
    (net (code "47") (name "Net-(U2-QP3)") (class "Default")
      (node (ref "LED1") (pin "14") (pinfunction "14_14") (pintype "passive"))
      (node (ref "U2") (pin "7") (pinfunction "QP3_7") (pintype "passive"))
    )
    (net (code "48") (name "Net-(U2-QP4)") (class "Default")
      (node (ref "LED1") (pin "15") (pinfunction "15_15") (pintype "passive"))
      (node (ref "U2") (pin "8") (pinfunction "QP4_8") (pintype "passive"))
    )
    (net (code "49") (name "Net-(U2-QP5)") (class "Default")
      (node (ref "LED1") (pin "16") (pinfunction "16_16") (pintype "passive"))
      (node (ref "U2") (pin "9") (pinfunction "QP5_9") (pintype "passive"))
    )
    (net (code "50") (name "Net-(U2-QP6)") (class "Default")
      (node (ref "LED1") (pin "17") (pinfunction "17_17") (pintype "passive"))
      (node (ref "U2") (pin "18") (pinfunction "QP6_18") (pintype "passive"))
    )
    (net (code "51") (name "Net-(U2-QP7)") (class "Default")
      (node (ref "LED1") (pin "18") (pinfunction "18_18") (pintype "passive"))
      (node (ref "U2") (pin "17") (pinfunction "QP7_17") (pintype "passive"))
    )
    (net (code "52") (name "Net-(U2-QP8)") (class "Default")
      (node (ref "LED1") (pin "19") (pinfunction "19_19") (pintype "passive"))
      (node (ref "U2") (pin "16") (pinfunction "QP8_16") (pintype "passive"))
    )
    (net (code "53") (name "Net-(U2-QP9)") (class "Default")
      (node (ref "LED1") (pin "20") (pinfunction "20_20") (pintype "passive"))
      (node (ref "U2") (pin "15") (pinfunction "QP9_15") (pintype "passive"))
    )
    (net (code "54") (name "Net-(U4-PB10)") (class "Default")
      (node (ref "J1") (pin "2") (pinfunction "2_2") (pintype "passive"))
      (node (ref "R22") (pin "2") (pinfunction "2_2") (pintype "passive"))
      (node (ref "U4") (pin "19") (pinfunction "PB10_19") (pintype "passive"))
    )
    (net (code "55") (name "Net-(U4-RESETN)") (class "Default")
      (node (ref "R21") (pin "2") (pinfunction "2_2") (pintype "passive"))
      (node (ref "U4") (pin "40") (pinfunction "RESETN_40") (pintype "passive"))
    )
    (net (code "56") (name "Net-(U5-COMP)") (class "Default")
      (node (ref "C21") (pin "1") (pinfunction "1_1") (pintype "passive"))
      (node (ref "U5") (pin "5") (pinfunction "COMP_5") (pintype "passive"))
    )
    (net (code "57") (name "Net-(U5-FB)") (class "Default")
      (node (ref "R23") (pin "1") (pinfunction "1_1") (pintype "passive"))
      (node (ref "R24") (pin "2") (pinfunction "2_2") (pintype "passive"))
      (node (ref "U5") (pin "4") (pinfunction "FB_4") (pintype "passive"))
    )
    (net (code "58") (name "Net-(U5-VSW)") (class "Default")
      (node (ref "L1") (pin "2") (pinfunction "2_2") (pintype "passive"))
      (node (ref "U5") (pin "8") (pinfunction "VSW_8") (pintype "passive"))
    )
    (net (code "59") (name "PROBE") (class "Default")
      (node (ref "P5") (pin "1") (pinfunction "1_1") (pintype "passive"))
      (node (ref "S5") (pin "1") (pinfunction "1_1") (pintype "passive"))
    )
    (net (code "60") (name "RED") (class "Default")
      (node (ref "R2") (pin "2") (pinfunction "2_2") (pintype "passive"))
      (node (ref "U4") (pin "16") (pinfunction "PA11_16") (pintype "passive"))
    )
    (net (code "61") (name "RESET") (class "Default")
      (node (ref "C8") (pin "1") (pinfunction "1_1") (pintype "passive"))
      (node (ref "PRGMR1") (pin "10") (pinfunction "RESET_10") (pintype "passive"))
      (node (ref "R20") (pin "1") (pinfunction "1_1") (pintype "passive"))
      (node (ref "R21") (pin "1") (pinfunction "1_1") (pintype "passive"))
      (node (ref "S6") (pin "1") (pinfunction "1_1") (pintype "passive"))
    )
    (net (code "62") (name "VPS") (class "Default")
      (node (ref "P4") (pin "1") (pinfunction "1_1") (pintype "passive"))
      (node (ref "S5") (pin "3") (pinfunction "3_3") (pintype "passive"))
    )
    (net (code "63") (name "WS2812B DATA") (class "Default")
      (node (ref "P3") (pin "2") (pinfunction "2_2") (pintype "passive"))
      (node (ref "R26") (pin "2") (pinfunction "2_2") (pintype "passive"))
    )
    (net (code "64") (name "WS2812B SIG") (class "Default")
      (node (ref "R26") (pin "1") (pinfunction "1_1") (pintype "passive"))
      (node (ref "U4") (pin "23") (pinfunction "PA14_23") (pintype "passive"))
    )
    (net (code "65") (name "White") (class "Default")
      (node (ref "R5") (pin "2") (pinfunction "2_2") (pintype "passive"))
      (node (ref "U4") (pin "13") (pinfunction "PA08_13") (pintype "passive"))
    )
    (net (code "66") (name "W{slash}RGB") (class "Default")
      (node (ref "R7") (pin "2") (pinfunction "2_2") (pintype "passive"))
      (node (ref "S2") (pin "2") (pinfunction "2_2") (pintype "passive"))
      (node (ref "U4") (pin "39") (pinfunction "PA27_39") (pintype "passive"))
    )
    (net (code "67") (name "unconnected-(PRGMR1-GND-Pad9)") (class "Default")
      (node (ref "PRGMR1") (pin "9") (pinfunction "GND_9") (pintype "passive"))
    )
    (net (code "68") (name "unconnected-(PRGMR1-KEY-Pad7)") (class "Default")
      (node (ref "PRGMR1") (pin "7") (pinfunction "KEY_7") (pintype "passive"))
    )
    (net (code "69") (name "unconnected-(PRGMR1-SWO-Pad6)") (class "Default")
      (node (ref "PRGMR1") (pin "6") (pinfunction "SWO_6") (pintype "passive"))
    )
    (net (code "70") (name "unconnected-(S6-Pad2)") (class "Default")
      (node (ref "S6") (pin "2") (pinfunction "2_2") (pintype "passive"))
    )
    (net (code "71") (name "unconnected-(U2-QP10-Pad14)") (class "Default")
      (node (ref "U2") (pin "14") (pinfunction "QP10_14") (pintype "passive"))
    )
    (net (code "72") (name "unconnected-(U2-QP11-Pad13)") (class "Default")
      (node (ref "U2") (pin "13") (pinfunction "QP11_13") (pintype "passive"))
    )
    (net (code "73") (name "unconnected-(U2-QS1-Pad11)") (class "Default")
      (node (ref "U2") (pin "11") (pinfunction "QS1_11") (pintype "passive"))
    )
    (net (code "74") (name "unconnected-(U2-QS2-Pad12)") (class "Default")
      (node (ref "U2") (pin "12") (pinfunction "QS2_12") (pintype "passive"))
    )
    (net (code "75") (name "unconnected-(U4-PA00-Pad1)") (class "Default")
      (node (ref "U4") (pin "1") (pinfunction "PA00_1") (pintype "passive"))
    )
    (net (code "76") (name "unconnected-(U4-PA01-Pad2)") (class "Default")
      (node (ref "U4") (pin "2") (pinfunction "PA01_2") (pintype "passive"))
    )
    (net (code "77") (name "unconnected-(U4-PA02-Pad3)") (class "Default")
      (node (ref "U4") (pin "3") (pinfunction "PA02_3") (pintype "passive"))
    )
    (net (code "78") (name "unconnected-(U4-PA06-Pad11)") (class "Default")
      (node (ref "U4") (pin "11") (pinfunction "PA06_11") (pintype "passive"))
    )
    (net (code "79") (name "unconnected-(U4-PA12-Pad21)") (class "Default")
      (node (ref "U4") (pin "21") (pinfunction "PA12_21") (pintype "passive"))
    )
    (net (code "80") (name "unconnected-(U4-PA13-Pad22)") (class "Default")
      (node (ref "U4") (pin "22") (pinfunction "PA13_22") (pintype "passive"))
    )
    (net (code "81") (name "unconnected-(U4-PA15-Pad24)") (class "Default")
      (node (ref "U4") (pin "24") (pinfunction "PA15_24") (pintype "passive"))
    )
    (net (code "82") (name "unconnected-(U4-PA16-Pad25)") (class "Default")
      (node (ref "U4") (pin "25") (pinfunction "PA16_25") (pintype "passive"))
    )
    (net (code "83") (name "unconnected-(U4-PA17-Pad26)") (class "Default")
      (node (ref "U4") (pin "26") (pinfunction "PA17_26") (pintype "passive"))
    )
    (net (code "84") (name "unconnected-(U4-PA18-Pad27)") (class "Default")
      (node (ref "U4") (pin "27") (pinfunction "PA18_27") (pintype "passive"))
    )
    (net (code "85") (name "unconnected-(U4-PA20-Pad29)") (class "Default")
      (node (ref "U4") (pin "29") (pinfunction "PA20_29") (pintype "passive"))
    )
    (net (code "86") (name "unconnected-(U4-PA22-Pad31)") (class "Default")
      (node (ref "U4") (pin "31") (pinfunction "PA22_31") (pintype "passive"))
    )
    (net (code "87") (name "unconnected-(U4-PA23-Pad32)") (class "Default")
      (node (ref "U4") (pin "32") (pinfunction "PA23_32") (pintype "passive"))
    )
    (net (code "88") (name "unconnected-(U4-PB08-Pad7)") (class "Default")
      (node (ref "U4") (pin "7") (pinfunction "PB08_7") (pintype "passive"))
    )
    (net (code "89") (name "unconnected-(U4-PB09-Pad8)") (class "Default")
      (node (ref "U4") (pin "8") (pinfunction "PB09_8") (pintype "passive"))
    )
    (net (code "90") (name "unconnected-(U4-PB11-Pad20)") (class "Default")
      (node (ref "U4") (pin "20") (pinfunction "PB11_20") (pintype "passive"))
    )
    (net (code "91") (name "unconnected-(U4-PB22-Pad37)") (class "Default")
      (node (ref "U4") (pin "37") (pinfunction "PB22_37") (pintype "passive"))
    )
    (net (code "92") (name "unconnected-(U4-PB23-Pad38)") (class "Default")
      (node (ref "U4") (pin "38") (pinfunction "PB23_38") (pintype "passive"))
    )
    (net (code "93") (name "unconnected-(U4-VSW-Pad43)") (class "Default")
      (node (ref "U4") (pin "43") (pinfunction "VSW_43") (pintype "passive"))
    )
    (net (code "94") (name "unconnected-(U5-PG-Pad7)") (class "Default")
      (node (ref "U5") (pin "7") (pinfunction "PG_7") (pintype "passive"))
    )
  )
)
